# KLineAdapter.net
KiCad netlist of a schematic drawn in EAGLE
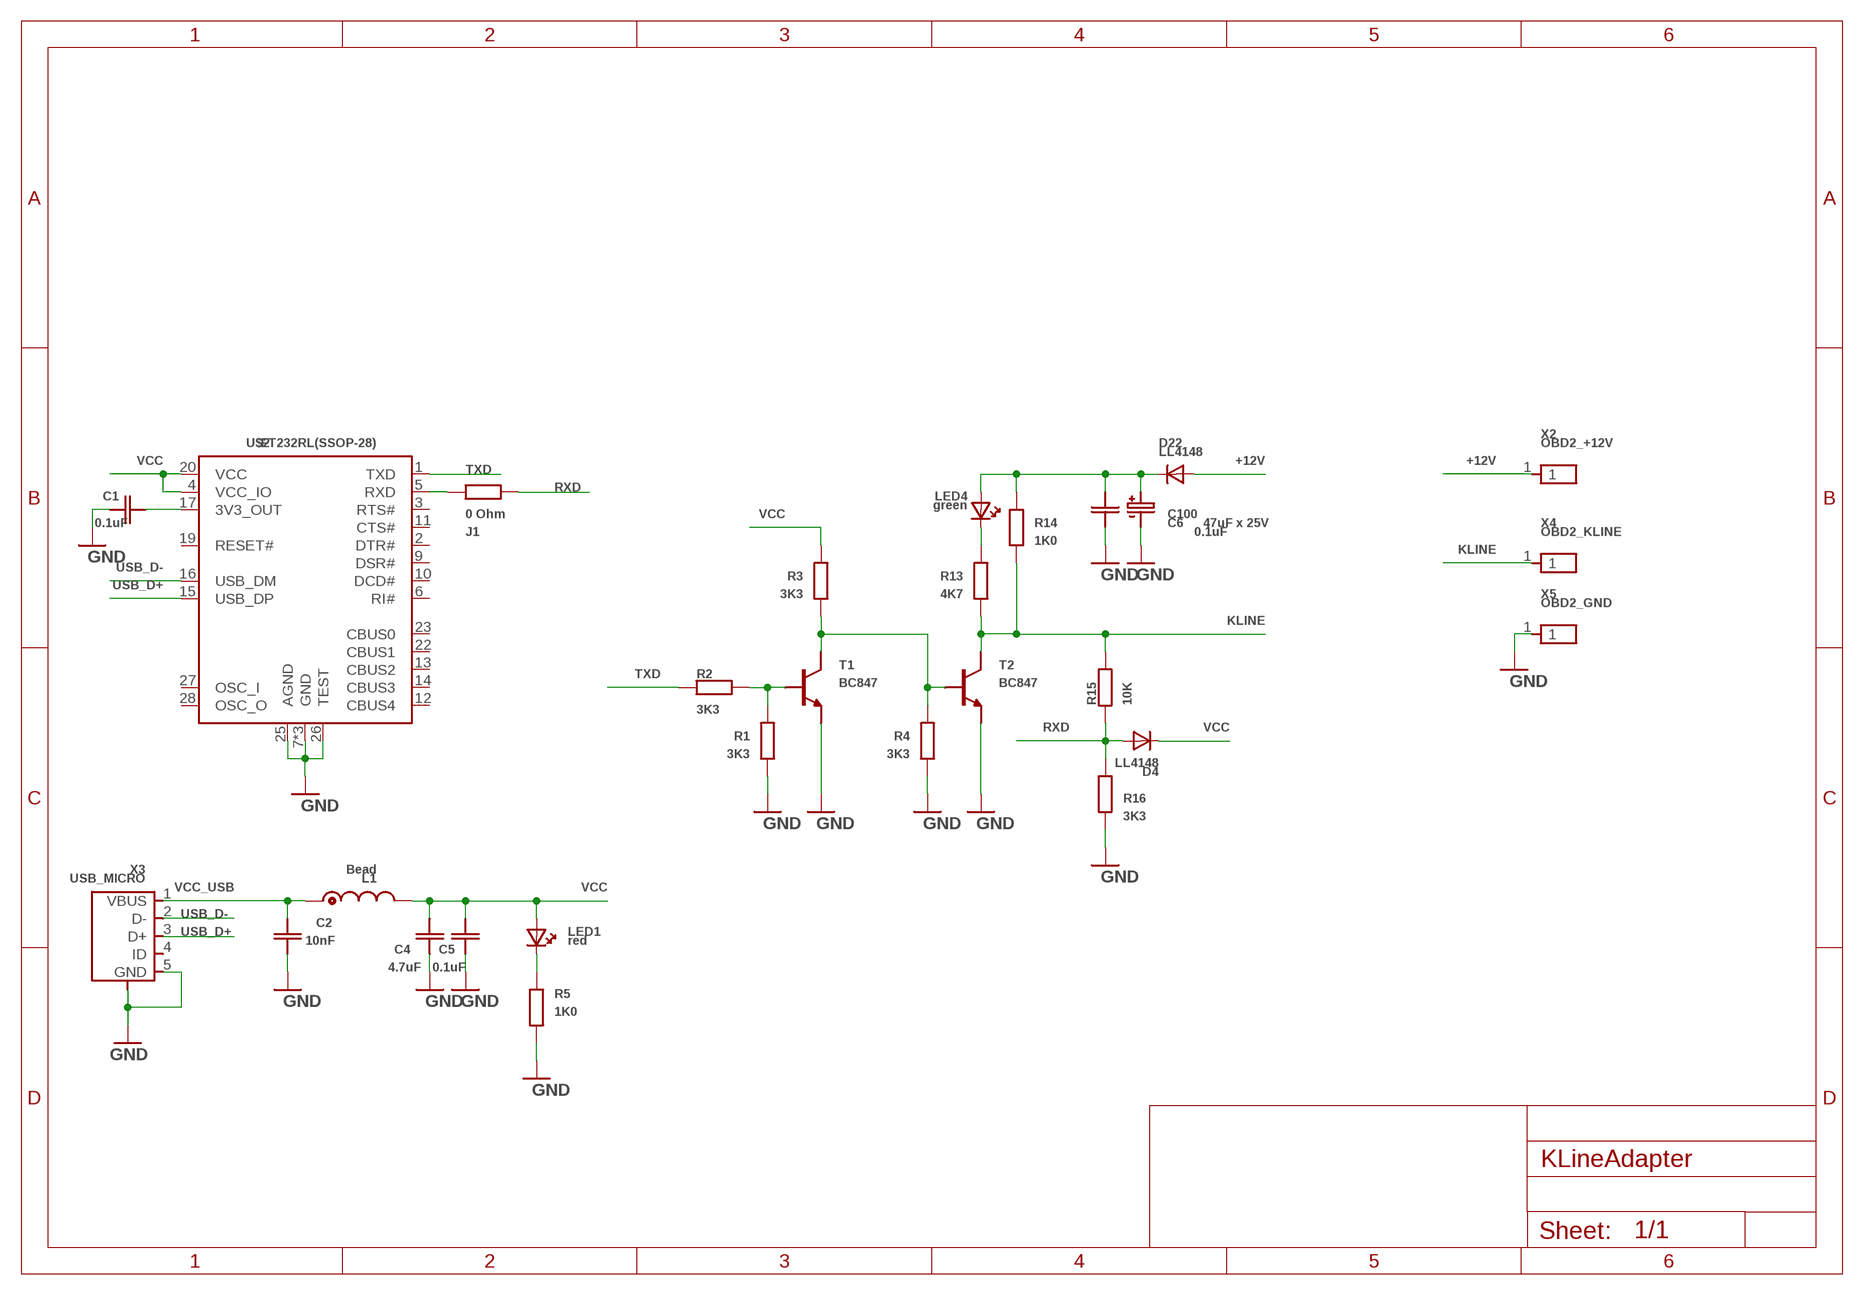
[diagram p0: schematic, sheet 1]

(export (version "E")
  (design (tool "Eeschema 10.0.6"))
  (components
    (comp (ref "C1")
      (value "0.1uF")
      (footprint "eagle-import:RSMD_0805")
      (libsource (lib "eagle-import") (part "CSMD_0805"))
    )
    (comp (ref "C2")
      (value "10nF")
      (footprint "eagle-import:RSMD_0805")
      (libsource (lib "eagle-import") (part "CSMD_0805"))
    )
    (comp (ref "C4")
      (value "4.7uF")
      (footprint "eagle-import:RSMD_1206")
      (libsource (lib "eagle-import") (part "CSMD_1206"))
    )
    (comp (ref "C5")
      (value "0.1uF")
      (footprint "eagle-import:RSMD_0805")
      (libsource (lib "eagle-import") (part "CSMD_0805"))
    )
    (comp (ref "C6")
      (value "0.1uF")
      (footprint "eagle-import:RSMD_0805")
      (libsource (lib "eagle-import") (part "CSMD_0805"))
    )
    (comp (ref "C100")
      (value "47uF x 25V")
      (footprint "eagle-import:CE_5.2MM")
      (libsource (lib "eagle-import") (part "CE5.2MM"))
    )
    (comp (ref "D4")
      (value "LL4148")
      (footprint "eagle-import:SOD-80")
      (libsource (lib "eagle-import") (part "LL4147SOD-80"))
    )
    (comp (ref "D22")
      (value "LL4148")
      (footprint "eagle-import:SOD-80")
      (libsource (lib "eagle-import") (part "LL4147SOD-80"))
    )
    (comp (ref "J1")
      (value "0 Ohm")
      (footprint "eagle-import:RSMD_0805")
      (libsource (lib "eagle-import") (part "RSMD_0805"))
    )
    (comp (ref "L1")
      (value "Bead")
      (footprint "eagle-import:RSMD_1206")
      (libsource (lib "eagle-import") (part "L"))
    )
    (comp (ref "LED1")
      (value "red")
      (footprint "eagle-import:LED_0805")
      (libsource (lib "eagle-import") (part "LED3MM(SMD0805)"))
    )
    (comp (ref "LED4")
      (value "green")
      (footprint "eagle-import:LED_0805")
      (libsource (lib "eagle-import") (part "LED3MM(SMD0805)"))
    )
    (comp (ref "R1")
      (value "3K3")
      (footprint "eagle-import:RSMD_0805")
      (libsource (lib "eagle-import") (part "RSMD_0805"))
    )
    (comp (ref "R2")
      (value "3K3")
      (footprint "eagle-import:RSMD_0805")
      (libsource (lib "eagle-import") (part "RSMD_0805"))
    )
    (comp (ref "R3")
      (value "3K3")
      (footprint "eagle-import:RSMD_0805")
      (libsource (lib "eagle-import") (part "RSMD_0805"))
    )
    (comp (ref "R4")
      (value "3K3")
      (footprint "eagle-import:RSMD_0805")
      (libsource (lib "eagle-import") (part "RSMD_0805"))
    )
    (comp (ref "R5")
      (value "1K0")
      (footprint "eagle-import:RSMD_0805")
      (libsource (lib "eagle-import") (part "RSMD_0805"))
    )
    (comp (ref "R13")
      (value "4K7")
      (footprint "eagle-import:RSMD_0805")
      (libsource (lib "eagle-import") (part "RSMD_0805"))
    )
    (comp (ref "R14")
      (value "1K0")
      (footprint "eagle-import:RSMD_0805")
      (libsource (lib "eagle-import") (part "RSMD_0805"))
    )
    (comp (ref "R15")
      (value "10K")
      (footprint "eagle-import:RSMD_0805")
      (libsource (lib "eagle-import") (part "RSMD_0805"))
    )
    (comp (ref "R16")
      (value "3K3")
      (footprint "eagle-import:RSMD_0805")
      (libsource (lib "eagle-import") (part "RSMD_0805"))
    )
    (comp (ref "T1")
      (value "BC847")
      (footprint "eagle-import:SOT23_SMALL_PADS")
      (libsource (lib "eagle-import") (part "BC847SOT23_SMALL_PADS"))
    )
    (comp (ref "T2")
      (value "BC847")
      (footprint "eagle-import:SOT23_SMALL_PADS")
      (libsource (lib "eagle-import") (part "BC847SOT23_SMALL_PADS"))
    )
    (comp (ref "U$2")
      (value "FT232RL(SSOP-28)")
      (footprint "eagle-import:SSOP-28")
      (libsource (lib "eagle-import") (part "FT232RL(SSOP-28)"))
    )
    (comp (ref "X2")
      (value "OBD2_+12V")
      (footprint "eagle-import:PIN1X1_3.5MM_PWR")
      (libsource (lib "eagle-import") (part "PIN1X13.5MM_PWR"))
    )
    (comp (ref "X3")
      (value "USB_MICRO")
      (footprint "eagle-import:USB_MICRO_TYPE_B")
      (libsource (lib "eagle-import") (part "USB_MICROMICRO"))
    )
    (comp (ref "X4")
      (value "OBD2_KLINE")
      (footprint "eagle-import:PIN1X1_3.5MM_PWR")
      (libsource (lib "eagle-import") (part "PIN1X13.5MM_PWR"))
    )
    (comp (ref "X5")
      (value "OBD2_GND")
      (footprint "eagle-import:PIN1X1_3.5MM_PWR")
      (libsource (lib "eagle-import") (part "PIN1X13.5MM_PWR"))
    )
  )
  (nets
    (net (code "1") (name "/+12V") (class "Default")
      (node (ref "D22") (pin "ANODE") (pinfunction "ANODE_ANODE") (pintype "passive"))
      (node (ref "X2") (pin "1") (pinfunction "1_1") (pintype "bidirectional"))
    )
    (net (code "2") (name "/KLINE") (class "Default")
      (node (ref "R13") (pin "PAD_0") (pinfunction "PIN0_PAD_0") (pintype "passive"))
      (node (ref "R14") (pin "PAD_0") (pinfunction "PIN0_PAD_0") (pintype "passive"))
      (node (ref "R15") (pin "PAD_1") (pinfunction "PIN1_PAD_1") (pintype "passive"))
      (node (ref "T2") (pin "3") (pinfunction "C_3") (pintype "bidirectional"))
      (node (ref "X4") (pin "1") (pinfunction "1_1") (pintype "bidirectional"))
    )
    (net (code "3") (name "/RXD") (class "Default")
      (node (ref "D4") (pin "ANODE") (pinfunction "ANODE_ANODE") (pintype "passive"))
      (node (ref "J1") (pin "PAD_1") (pinfunction "PIN1_PAD_1") (pintype "passive"))
      (node (ref "R15") (pin "PAD_0") (pinfunction "PIN0_PAD_0") (pintype "passive"))
      (node (ref "R16") (pin "PAD_1") (pinfunction "PIN1_PAD_1") (pintype "passive"))
    )
    (net (code "4") (name "/TXD") (class "Default")
      (node (ref "R2") (pin "PAD_0") (pinfunction "PIN0_PAD_0") (pintype "passive"))
      (node (ref "U$2") (pin "1") (pinfunction "TXD_1") (pintype "bidirectional"))
    )
    (net (code "5") (name "/USB_D+") (class "Default")
      (node (ref "U$2") (pin "15") (pinfunction "USB_DP_15") (pintype "bidirectional"))
      (node (ref "X3") (pin "3") (pinfunction "D+_3") (pintype "bidirectional"))
    )
    (net (code "6") (name "/USB_D-") (class "Default")
      (node (ref "U$2") (pin "16") (pinfunction "USB_DM_16") (pintype "bidirectional"))
      (node (ref "X3") (pin "2") (pinfunction "D-_2") (pintype "bidirectional"))
    )
    (net (code "7") (name "/VCC") (class "Default")
      (node (ref "C4") (pin "PAD_1") (pinfunction "PIN1_PAD_1") (pintype "bidirectional"))
      (node (ref "C5") (pin "PAD_1") (pinfunction "PIN1_PAD_1") (pintype "bidirectional"))
      (node (ref "D4") (pin "CATHODE") (pinfunction "CATHODE_CATHODE") (pintype "passive"))
      (node (ref "L1") (pin "PAD_0") (pinfunction "END_PAD_0") (pintype "bidirectional"))
      (node (ref "LED1") (pin "ANODE") (pinfunction "ANODE_ANODE") (pintype "passive"))
      (node (ref "R3") (pin "PAD_1") (pinfunction "PIN1_PAD_1") (pintype "passive"))
      (node (ref "U$2") (pin "20") (pinfunction "VCC_20") (pintype "bidirectional"))
      (node (ref "U$2") (pin "4") (pinfunction "VCC_IO_4") (pintype "bidirectional"))
    )
    (net (code "8") (name "/VCC_USB") (class "Default")
      (node (ref "C2") (pin "PAD_1") (pinfunction "PIN1_PAD_1") (pintype "bidirectional"))
      (node (ref "L1") (pin "PAD_1") (pinfunction "START_PAD_1") (pintype "bidirectional"))
      (node (ref "X3") (pin "1") (pinfunction "VBUS_1") (pintype "bidirectional"))
    )
    (net (code "9") (name "GND") (class "Default")
      (node (ref "C1") (pin "PAD_0") (pinfunction "PIN0_PAD_0") (pintype "bidirectional"))
      (node (ref "C100") (pin "MINUS") (pinfunction "MINUS_MINUS") (pintype "bidirectional"))
      (node (ref "C2") (pin "PAD_0") (pinfunction "PIN0_PAD_0") (pintype "bidirectional"))
      (node (ref "C4") (pin "PAD_0") (pinfunction "PIN0_PAD_0") (pintype "bidirectional"))
      (node (ref "C5") (pin "PAD_0") (pinfunction "PIN0_PAD_0") (pintype "bidirectional"))
      (node (ref "C6") (pin "PAD_0") (pinfunction "PIN0_PAD_0") (pintype "bidirectional"))
      (node (ref "R1") (pin "PAD_1") (pinfunction "PIN1_PAD_1") (pintype "passive"))
      (node (ref "R16") (pin "PAD_0") (pinfunction "PIN0_PAD_0") (pintype "passive"))
      (node (ref "R4") (pin "PAD_1") (pinfunction "PIN1_PAD_1") (pintype "passive"))
      (node (ref "R5") (pin "PAD_0") (pinfunction "PIN0_PAD_0") (pintype "passive"))
      (node (ref "T1") (pin "2") (pinfunction "E_2") (pintype "bidirectional"))
      (node (ref "T2") (pin "2") (pinfunction "E_2") (pintype "bidirectional"))
      (node (ref "U$2") (pin "18") (pinfunction "GND_18") (pintype "bidirectional"))
      (node (ref "U$2") (pin "21") (pinfunction "GND_21") (pintype "bidirectional"))
      (node (ref "U$2") (pin "25") (pinfunction "AGND_25") (pintype "bidirectional"))
      (node (ref "U$2") (pin "26") (pinfunction "TEST_26") (pintype "bidirectional"))
      (node (ref "U$2") (pin "7") (pinfunction "GND_7") (pintype "bidirectional"))
      (node (ref "X3") (pin "5") (pinfunction "GND_5") (pintype "bidirectional"))
      (node (ref "X3") (pin "PACKAGE1") (pinfunction "PACKAGE_PACKAGE1") (pintype "bidirectional"))
      (node (ref "X3") (pin "PACKAGE2") (pinfunction "PACKAGE_PACKAGE2") (pintype "bidirectional"))
      (node (ref "X3") (pin "PACKAGE3") (pinfunction "PACKAGE_PACKAGE3") (pintype "bidirectional"))
      (node (ref "X3") (pin "PACKAGE4") (pinfunction "PACKAGE_PACKAGE4") (pintype "bidirectional"))
      (node (ref "X3") (pin "PACKAGE5") (pinfunction "PACKAGE_PACKAGE5") (pintype "bidirectional"))
      (node (ref "X5") (pin "1") (pinfunction "1_1") (pintype "bidirectional"))
    )
    (net (code "10") (name "Net-(C1-PIN1)") (class "Default")
      (node (ref "C1") (pin "PAD_1") (pinfunction "PIN1_PAD_1") (pintype "bidirectional"))
      (node (ref "U$2") (pin "17") (pinfunction "3V3_OUT_17") (pintype "bidirectional"))
    )
    (net (code "11") (name "Net-(C6-PIN1)") (class "Default")
      (node (ref "C100") (pin "PLUS") (pinfunction "PLUS_PLUS") (pintype "bidirectional"))
      (node (ref "C6") (pin "PAD_1") (pinfunction "PIN1_PAD_1") (pintype "bidirectional"))
      (node (ref "D22") (pin "CATHODE") (pinfunction "CATHODE_CATHODE") (pintype "passive"))
      (node (ref "LED4") (pin "ANODE") (pinfunction "ANODE_ANODE") (pintype "passive"))
      (node (ref "R14") (pin "PAD_1") (pinfunction "PIN1_PAD_1") (pintype "passive"))
    )
    (net (code "12") (name "Net-(J1-PIN0)") (class "Default")
      (node (ref "J1") (pin "PAD_0") (pinfunction "PIN0_PAD_0") (pintype "passive"))
      (node (ref "U$2") (pin "5") (pinfunction "RXD_5") (pintype "bidirectional"))
    )
    (net (code "13") (name "Net-(R1-PIN0)") (class "Default")
      (node (ref "R1") (pin "PAD_0") (pinfunction "PIN0_PAD_0") (pintype "passive"))
      (node (ref "R2") (pin "PAD_1") (pinfunction "PIN1_PAD_1") (pintype "passive"))
      (node (ref "T1") (pin "1") (pinfunction "B_1") (pintype "bidirectional"))
    )
    (net (code "14") (name "Net-(R3-PIN0)") (class "Default")
      (node (ref "R3") (pin "PAD_0") (pinfunction "PIN0_PAD_0") (pintype "passive"))
      (node (ref "R4") (pin "PAD_0") (pinfunction "PIN0_PAD_0") (pintype "passive"))
      (node (ref "T1") (pin "3") (pinfunction "C_3") (pintype "bidirectional"))
      (node (ref "T2") (pin "1") (pinfunction "B_1") (pintype "bidirectional"))
    )
    (net (code "15") (name "Net-(R5-PIN1)") (class "Default")
      (node (ref "LED1") (pin "CATHODE") (pinfunction "CATHODE_CATHODE") (pintype "passive"))
      (node (ref "R5") (pin "PAD_1") (pinfunction "PIN1_PAD_1") (pintype "passive"))
    )
    (net (code "16") (name "Net-(R13-PIN1)") (class "Default")
      (node (ref "LED4") (pin "CATHODE") (pinfunction "CATHODE_CATHODE") (pintype "passive"))
      (node (ref "R13") (pin "PAD_1") (pinfunction "PIN1_PAD_1") (pintype "passive"))
    )
    (net (code "17") (name "unconnected-(U$2-CBUS0-Pad23)") (class "Default")
      (node (ref "U$2") (pin "23") (pinfunction "CBUS0_23") (pintype "bidirectional"))
    )
    (net (code "18") (name "unconnected-(U$2-CBUS1-Pad22)") (class "Default")
      (node (ref "U$2") (pin "22") (pinfunction "CBUS1_22") (pintype "bidirectional"))
    )
    (net (code "19") (name "unconnected-(U$2-CBUS2-Pad13)") (class "Default")
      (node (ref "U$2") (pin "13") (pinfunction "CBUS2_13") (pintype "bidirectional"))
    )
    (net (code "20") (name "unconnected-(U$2-CBUS3-Pad14)") (class "Default")
      (node (ref "U$2") (pin "14") (pinfunction "CBUS3_14") (pintype "bidirectional"))
    )
    (net (code "21") (name "unconnected-(U$2-CBUS4-Pad12)") (class "Default")
      (node (ref "U$2") (pin "12") (pinfunction "CBUS4_12") (pintype "bidirectional"))
    )
    (net (code "22") (name "unconnected-(U$2-CTS#-Pad11)") (class "Default")
      (node (ref "U$2") (pin "11") (pinfunction "CTS#_11") (pintype "bidirectional"))
    )
    (net (code "23") (name "unconnected-(U$2-DCD#-Pad10)") (class "Default")
      (node (ref "U$2") (pin "10") (pinfunction "DCD#_10") (pintype "bidirectional"))
    )
    (net (code "24") (name "unconnected-(U$2-DSR#-Pad9)") (class "Default")
      (node (ref "U$2") (pin "9") (pinfunction "DSR#_9") (pintype "bidirectional"))
    )
    (net (code "25") (name "unconnected-(U$2-DTR#-Pad2)") (class "Default")
      (node (ref "U$2") (pin "2") (pinfunction "DTR#_2") (pintype "bidirectional"))
    )
    (net (code "26") (name "unconnected-(U$2-OSC_I-Pad27)") (class "Default")
      (node (ref "U$2") (pin "27") (pinfunction "OSC_I_27") (pintype "bidirectional"))
    )
    (net (code "27") (name "unconnected-(U$2-OSC_O-Pad28)") (class "Default")
      (node (ref "U$2") (pin "28") (pinfunction "OSC_O_28") (pintype "bidirectional"))
    )
    (net (code "28") (name "unconnected-(U$2-RESET#-Pad19)") (class "Default")
      (node (ref "U$2") (pin "19") (pinfunction "RESET#_19") (pintype "bidirectional"))
    )
    (net (code "29") (name "unconnected-(U$2-RI#-Pad6)") (class "Default")
      (node (ref "U$2") (pin "6") (pinfunction "RI#_6") (pintype "bidirectional"))
    )
    (net (code "30") (name "unconnected-(U$2-RTS#-Pad3)") (class "Default")
      (node (ref "U$2") (pin "3") (pinfunction "RTS#_3") (pintype "bidirectional"))
    )
    (net (code "31") (name "unconnected-(X3-ID-Pad4)") (class "Default")
      (node (ref "X3") (pin "4") (pinfunction "ID_4") (pintype "bidirectional"))
    )
  )
)
